# guider-shield.net
KiCad netlist of a schematic drawn in EAGLE
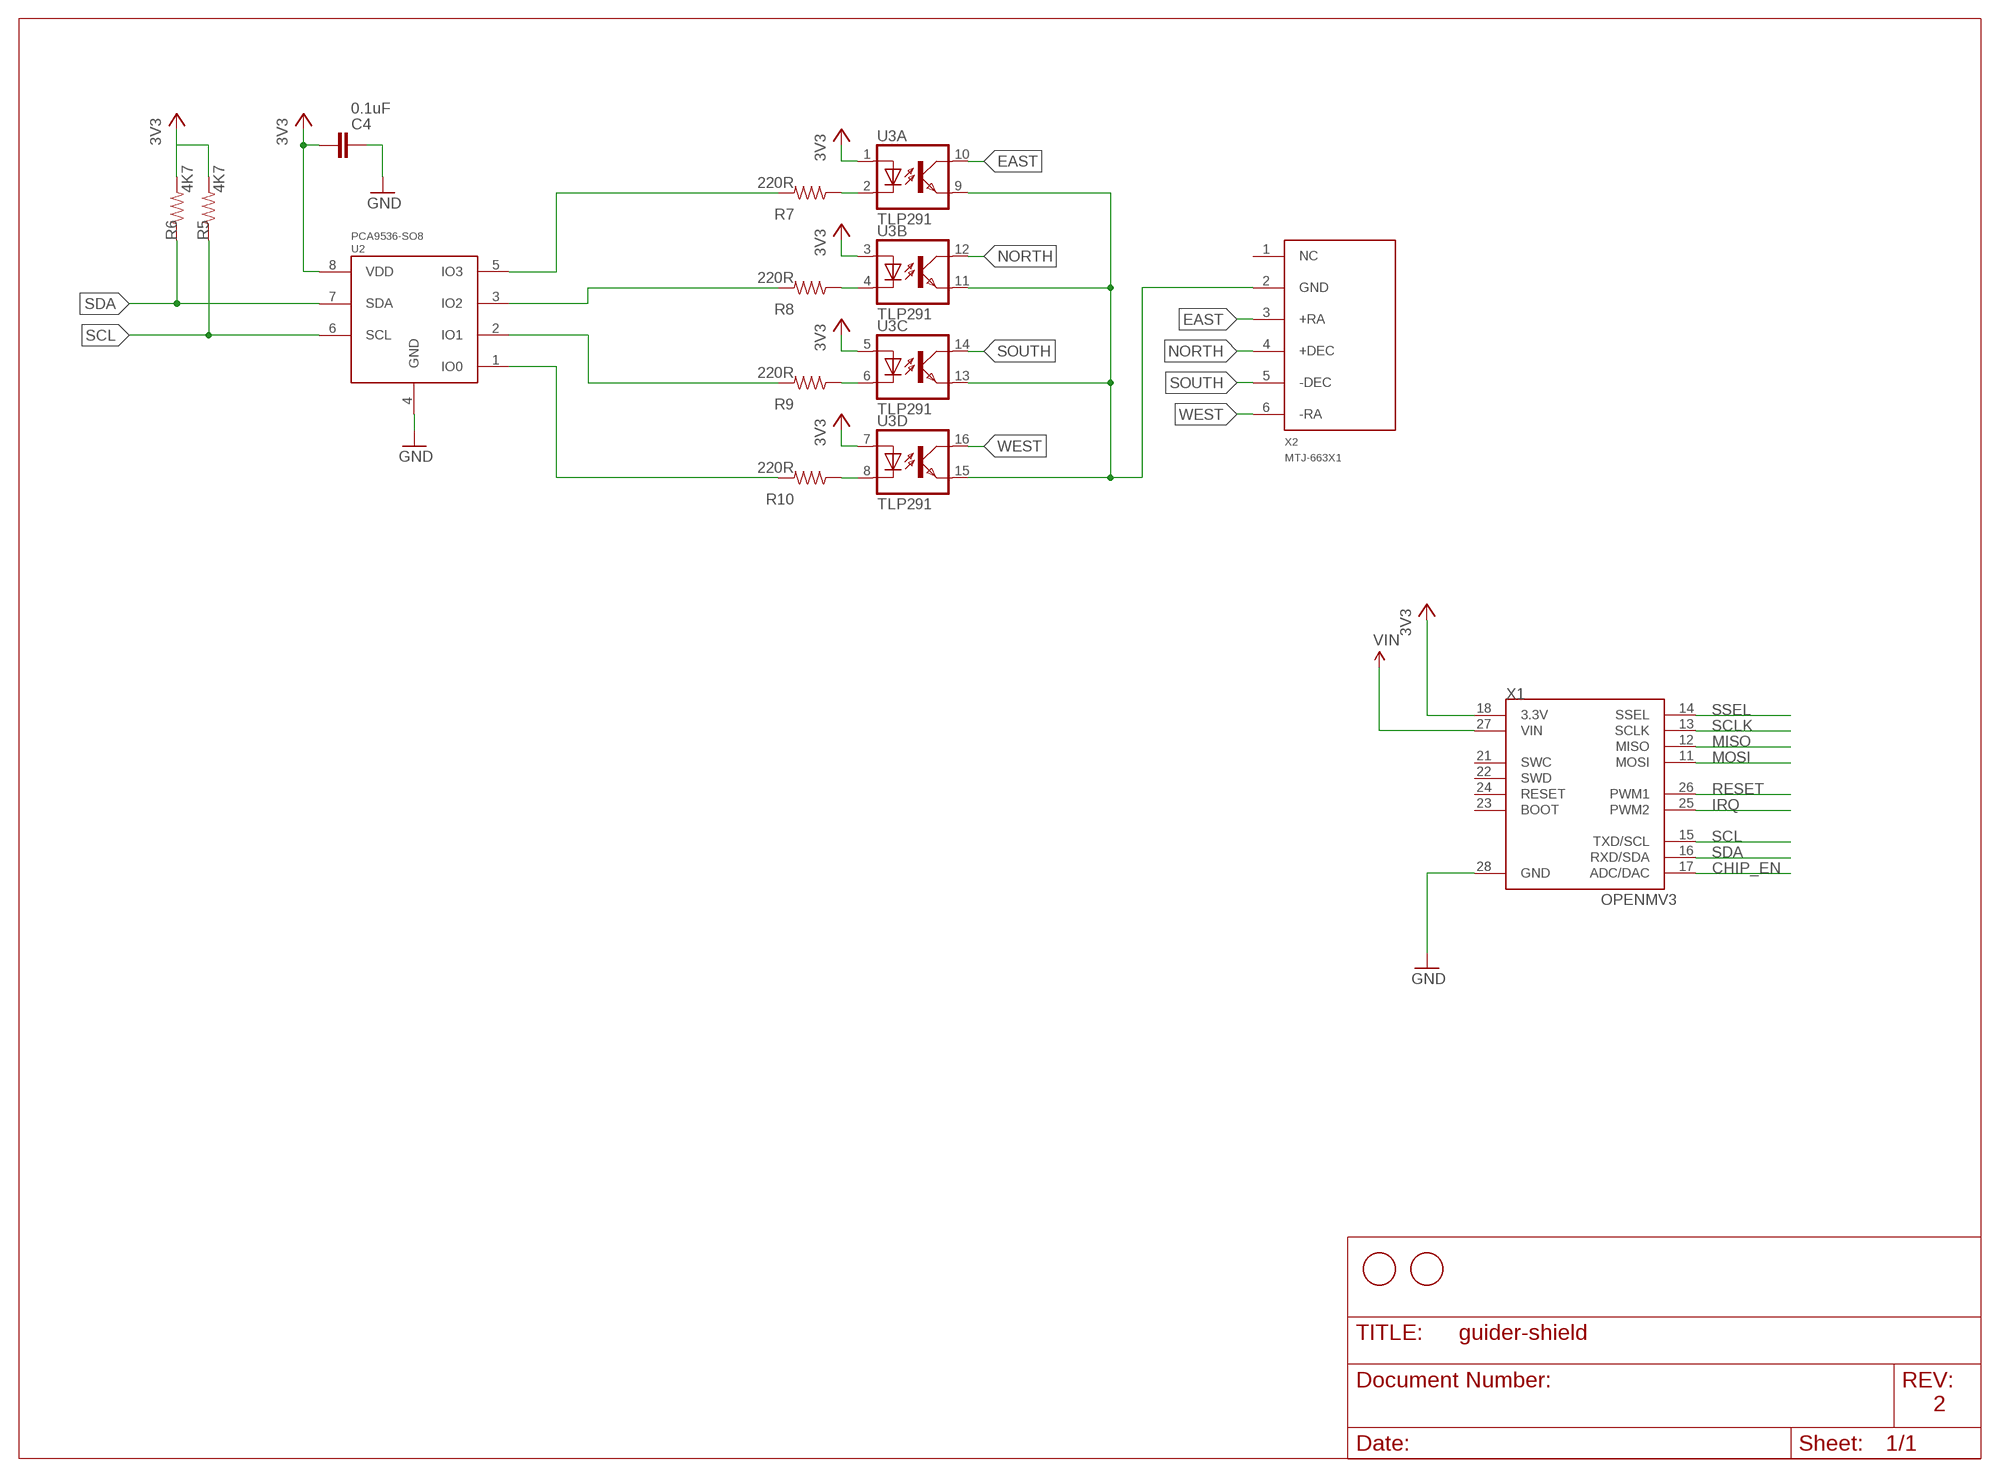
[diagram p0: schematic, sheet 1]

(export (version "E")
  (design (tool "Eeschema 10.0.6"))
  (components
    (comp (ref "C4")
      (value "0.1uF")
      (footprint "eagle-import:0603-CAP")
      (libsource (lib "eagle-import") (part "CAP0603-CAP"))
    )
    (comp (ref "R5")
      (value "4K7")
      (footprint "eagle-import:0603-RES")
      (libsource (lib "eagle-import") (part "RESISTOR0603-RES"))
    )
    (comp (ref "R6")
      (value "4K7")
      (footprint "eagle-import:0603-RES")
      (libsource (lib "eagle-import") (part "RESISTOR0603-RES"))
    )
    (comp (ref "R7")
      (value "220R")
      (footprint "eagle-import:0603-RES")
      (libsource (lib "eagle-import") (part "RESISTOR0603-RES"))
    )
    (comp (ref "R8")
      (value "220R")
      (footprint "eagle-import:0603-RES")
      (libsource (lib "eagle-import") (part "RESISTOR0603-RES"))
    )
    (comp (ref "R9")
      (value "220R")
      (footprint "eagle-import:0603-RES")
      (libsource (lib "eagle-import") (part "RESISTOR0603-RES"))
    )
    (comp (ref "R10")
      (value "220R")
      (footprint "eagle-import:0603-RES")
      (libsource (lib "eagle-import") (part "RESISTOR0603-RES"))
    )
    (comp (ref "U$1")
      (value "FIDUCIAL")
      (footprint "eagle-import:FIDUCIAL_1MM")
      (libsource (lib "eagle-import") (part "FIDUCIAL"))
    )
    (comp (ref "U$2")
      (value "FIDUCIAL")
      (footprint "eagle-import:FIDUCIAL_1MM")
      (libsource (lib "eagle-import") (part "FIDUCIAL"))
    )
    (comp (ref "U2")
      (value "PCA9536-SO8")
      (footprint "eagle-import:SO08")
      (libsource (lib "eagle-import") (part "PCA9536-SO8"))
    )
    (comp (ref "U3")
      (value "TLP291")
      (footprint "eagle-import:SO016")
      (libsource (lib "eagle-import") (part "TLP283-4-SO016"))
    )
    (comp (ref "X1")
      (value "OPENMV3")
      (footprint "eagle-import:OPENMV3")
      (libsource (lib "eagle-import") (part "OPENMV3"))
    )
    (comp (ref "X2")
      (value "MTJ-663X1")
      (footprint "eagle-import:MTJ-663X1")
      (libsource (lib "eagle-import") (part "ST-4-MTJ-663X1"))
    )
  )
  (nets
    (net (code "1") (name "/CHIP_EN") (class "Default")
      (node (ref "X1") (pin "17") (pinfunction "ADC/DAC_17") (pintype "bidirectional"))
    )
    (net (code "2") (name "/IRQ") (class "Default")
      (node (ref "X1") (pin "25") (pinfunction "PWM2_25") (pintype "bidirectional"))
    )
    (net (code "3") (name "/MISO") (class "Default")
      (node (ref "X1") (pin "12") (pinfunction "MISO_12") (pintype "bidirectional"))
    )
    (net (code "4") (name "/MOSI") (class "Default")
      (node (ref "X1") (pin "11") (pinfunction "MOSI_11") (pintype "bidirectional"))
    )
    (net (code "5") (name "/RESET") (class "Default")
      (node (ref "X1") (pin "26") (pinfunction "PWM1_26") (pintype "bidirectional"))
    )
    (net (code "6") (name "/SCLK") (class "Default")
      (node (ref "X1") (pin "13") (pinfunction "SCLK_13") (pintype "bidirectional"))
    )
    (net (code "7") (name "/SSEL") (class "Default")
      (node (ref "X1") (pin "14") (pinfunction "SSEL_14") (pintype "bidirectional"))
    )
    (net (code "8") (name "3V3") (class "Default")
      (node (ref "C4") (pin "1") (pinfunction "1_1") (pintype "passive"))
      (node (ref "R5") (pin "2") (pinfunction "2_2") (pintype "passive"))
      (node (ref "R6") (pin "2") (pinfunction "2_2") (pintype "passive"))
      (node (ref "U2") (pin "8") (pinfunction "VDD_8") (pintype "input"))
      (node (ref "U3") (pin "1") (pinfunction "A_1") (pintype "passive"))
      (node (ref "U3") (pin "3") (pinfunction "A_3") (pintype "passive"))
      (node (ref "U3") (pin "5") (pinfunction "A_5") (pintype "passive"))
      (node (ref "U3") (pin "7") (pinfunction "A_7") (pintype "passive"))
      (node (ref "X1") (pin "18") (pinfunction "3.3V_18") (pintype "power_in"))
    )
    (net (code "9") (name "EAST") (class "Default")
      (node (ref "U3") (pin "10") (pinfunction "COL_10") (pintype "passive"))
      (node (ref "X2") (pin "3") (pinfunction "+RA_3") (pintype "input"))
    )
    (net (code "10") (name "GND") (class "Default")
      (node (ref "C4") (pin "2") (pinfunction "2_2") (pintype "passive"))
      (node (ref "U2") (pin "4") (pinfunction "GND_4") (pintype "input"))
      (node (ref "X1") (pin "28") (pinfunction "GND_28") (pintype "power_in"))
    )
    (net (code "11") (name "NORTH") (class "Default")
      (node (ref "U3") (pin "12") (pinfunction "COL_12") (pintype "passive"))
      (node (ref "X2") (pin "4") (pinfunction "+DEC_4") (pintype "input"))
    )
    (net (code "12") (name "Net-(U2-IO0)") (class "Default")
      (node (ref "R10") (pin "2") (pinfunction "2_2") (pintype "passive"))
      (node (ref "U2") (pin "1") (pinfunction "IO0_1") (pintype "bidirectional"))
    )
    (net (code "13") (name "Net-(U2-IO1)") (class "Default")
      (node (ref "R9") (pin "2") (pinfunction "2_2") (pintype "passive"))
      (node (ref "U2") (pin "2") (pinfunction "IO1_2") (pintype "bidirectional"))
    )
    (net (code "14") (name "Net-(U2-IO2)") (class "Default")
      (node (ref "R8") (pin "2") (pinfunction "2_2") (pintype "passive"))
      (node (ref "U2") (pin "3") (pinfunction "IO2_3") (pintype "bidirectional"))
    )
    (net (code "15") (name "Net-(U2-IO3)") (class "Default")
      (node (ref "R7") (pin "2") (pinfunction "2_2") (pintype "passive"))
      (node (ref "U2") (pin "5") (pinfunction "IO3_5") (pintype "bidirectional"))
    )
    (net (code "16") (name "Net-(U3A-C)") (class "Default")
      (node (ref "R7") (pin "1") (pinfunction "1_1") (pintype "passive"))
      (node (ref "U3") (pin "2") (pinfunction "C_2") (pintype "passive"))
    )
    (net (code "17") (name "Net-(U3A-EMIT)") (class "Default")
      (node (ref "U3") (pin "11") (pinfunction "EMIT_11") (pintype "passive"))
      (node (ref "U3") (pin "13") (pinfunction "EMIT_13") (pintype "passive"))
      (node (ref "U3") (pin "15") (pinfunction "EMIT_15") (pintype "passive"))
      (node (ref "U3") (pin "9") (pinfunction "EMIT_9") (pintype "passive"))
      (node (ref "X2") (pin "2") (pinfunction "GND_2") (pintype "input"))
    )
    (net (code "18") (name "Net-(U3B-C)") (class "Default")
      (node (ref "R8") (pin "1") (pinfunction "1_1") (pintype "passive"))
      (node (ref "U3") (pin "4") (pinfunction "C_4") (pintype "passive"))
    )
    (net (code "19") (name "Net-(U3C-C)") (class "Default")
      (node (ref "R9") (pin "1") (pinfunction "1_1") (pintype "passive"))
      (node (ref "U3") (pin "6") (pinfunction "C_6") (pintype "passive"))
    )
    (net (code "20") (name "Net-(U3D-C)") (class "Default")
      (node (ref "R10") (pin "1") (pinfunction "1_1") (pintype "passive"))
      (node (ref "U3") (pin "8") (pinfunction "C_8") (pintype "passive"))
    )
    (net (code "21") (name "SCL") (class "Default")
      (node (ref "R5") (pin "1") (pinfunction "1_1") (pintype "passive"))
      (node (ref "U2") (pin "6") (pinfunction "SCL_6") (pintype "bidirectional"))
      (node (ref "X1") (pin "15") (pinfunction "TXD/SCL_15") (pintype "bidirectional"))
    )
    (net (code "22") (name "SDA") (class "Default")
      (node (ref "R6") (pin "1") (pinfunction "1_1") (pintype "passive"))
      (node (ref "U2") (pin "7") (pinfunction "SDA_7") (pintype "bidirectional"))
      (node (ref "X1") (pin "16") (pinfunction "RXD/SDA_16") (pintype "bidirectional"))
    )
    (net (code "23") (name "SOUTH") (class "Default")
      (node (ref "U3") (pin "14") (pinfunction "COL_14") (pintype "passive"))
      (node (ref "X2") (pin "5") (pinfunction "-DEC_5") (pintype "input"))
    )
    (net (code "24") (name "VIN") (class "Default")
      (node (ref "X1") (pin "27") (pinfunction "VIN_27") (pintype "power_in"))
    )
    (net (code "25") (name "WEST") (class "Default")
      (node (ref "U3") (pin "16") (pinfunction "COL_16") (pintype "passive"))
      (node (ref "X2") (pin "6") (pinfunction "-RA_6") (pintype "input"))
    )
    (net (code "26") (name "unconnected-(X1-BOOT-Pad23)") (class "Default")
      (node (ref "X1") (pin "23") (pinfunction "BOOT_23") (pintype "bidirectional"))
    )
    (net (code "27") (name "unconnected-(X1-RESET-Pad24)") (class "Default")
      (node (ref "X1") (pin "24") (pinfunction "RESET_24") (pintype "bidirectional"))
    )
    (net (code "28") (name "unconnected-(X1-SWC-Pad21)") (class "Default")
      (node (ref "X1") (pin "21") (pinfunction "SWC_21") (pintype "bidirectional"))
    )
    (net (code "29") (name "unconnected-(X1-SWD-Pad22)") (class "Default")
      (node (ref "X1") (pin "22") (pinfunction "SWD_22") (pintype "bidirectional"))
    )
    (net (code "30") (name "unconnected-(X2-NC-Pad1)") (class "Default")
      (node (ref "X2") (pin "1") (pinfunction "NC_1") (pintype "no_connect"))
    )
  )
)
